# PiHAT.net
KiCad netlist of a schematic drawn in EAGLE
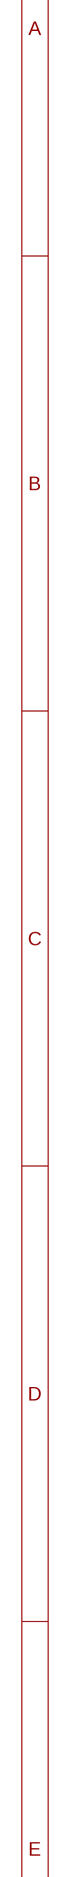
[diagram p0: schematic, sheet 1, part 1 of 2]
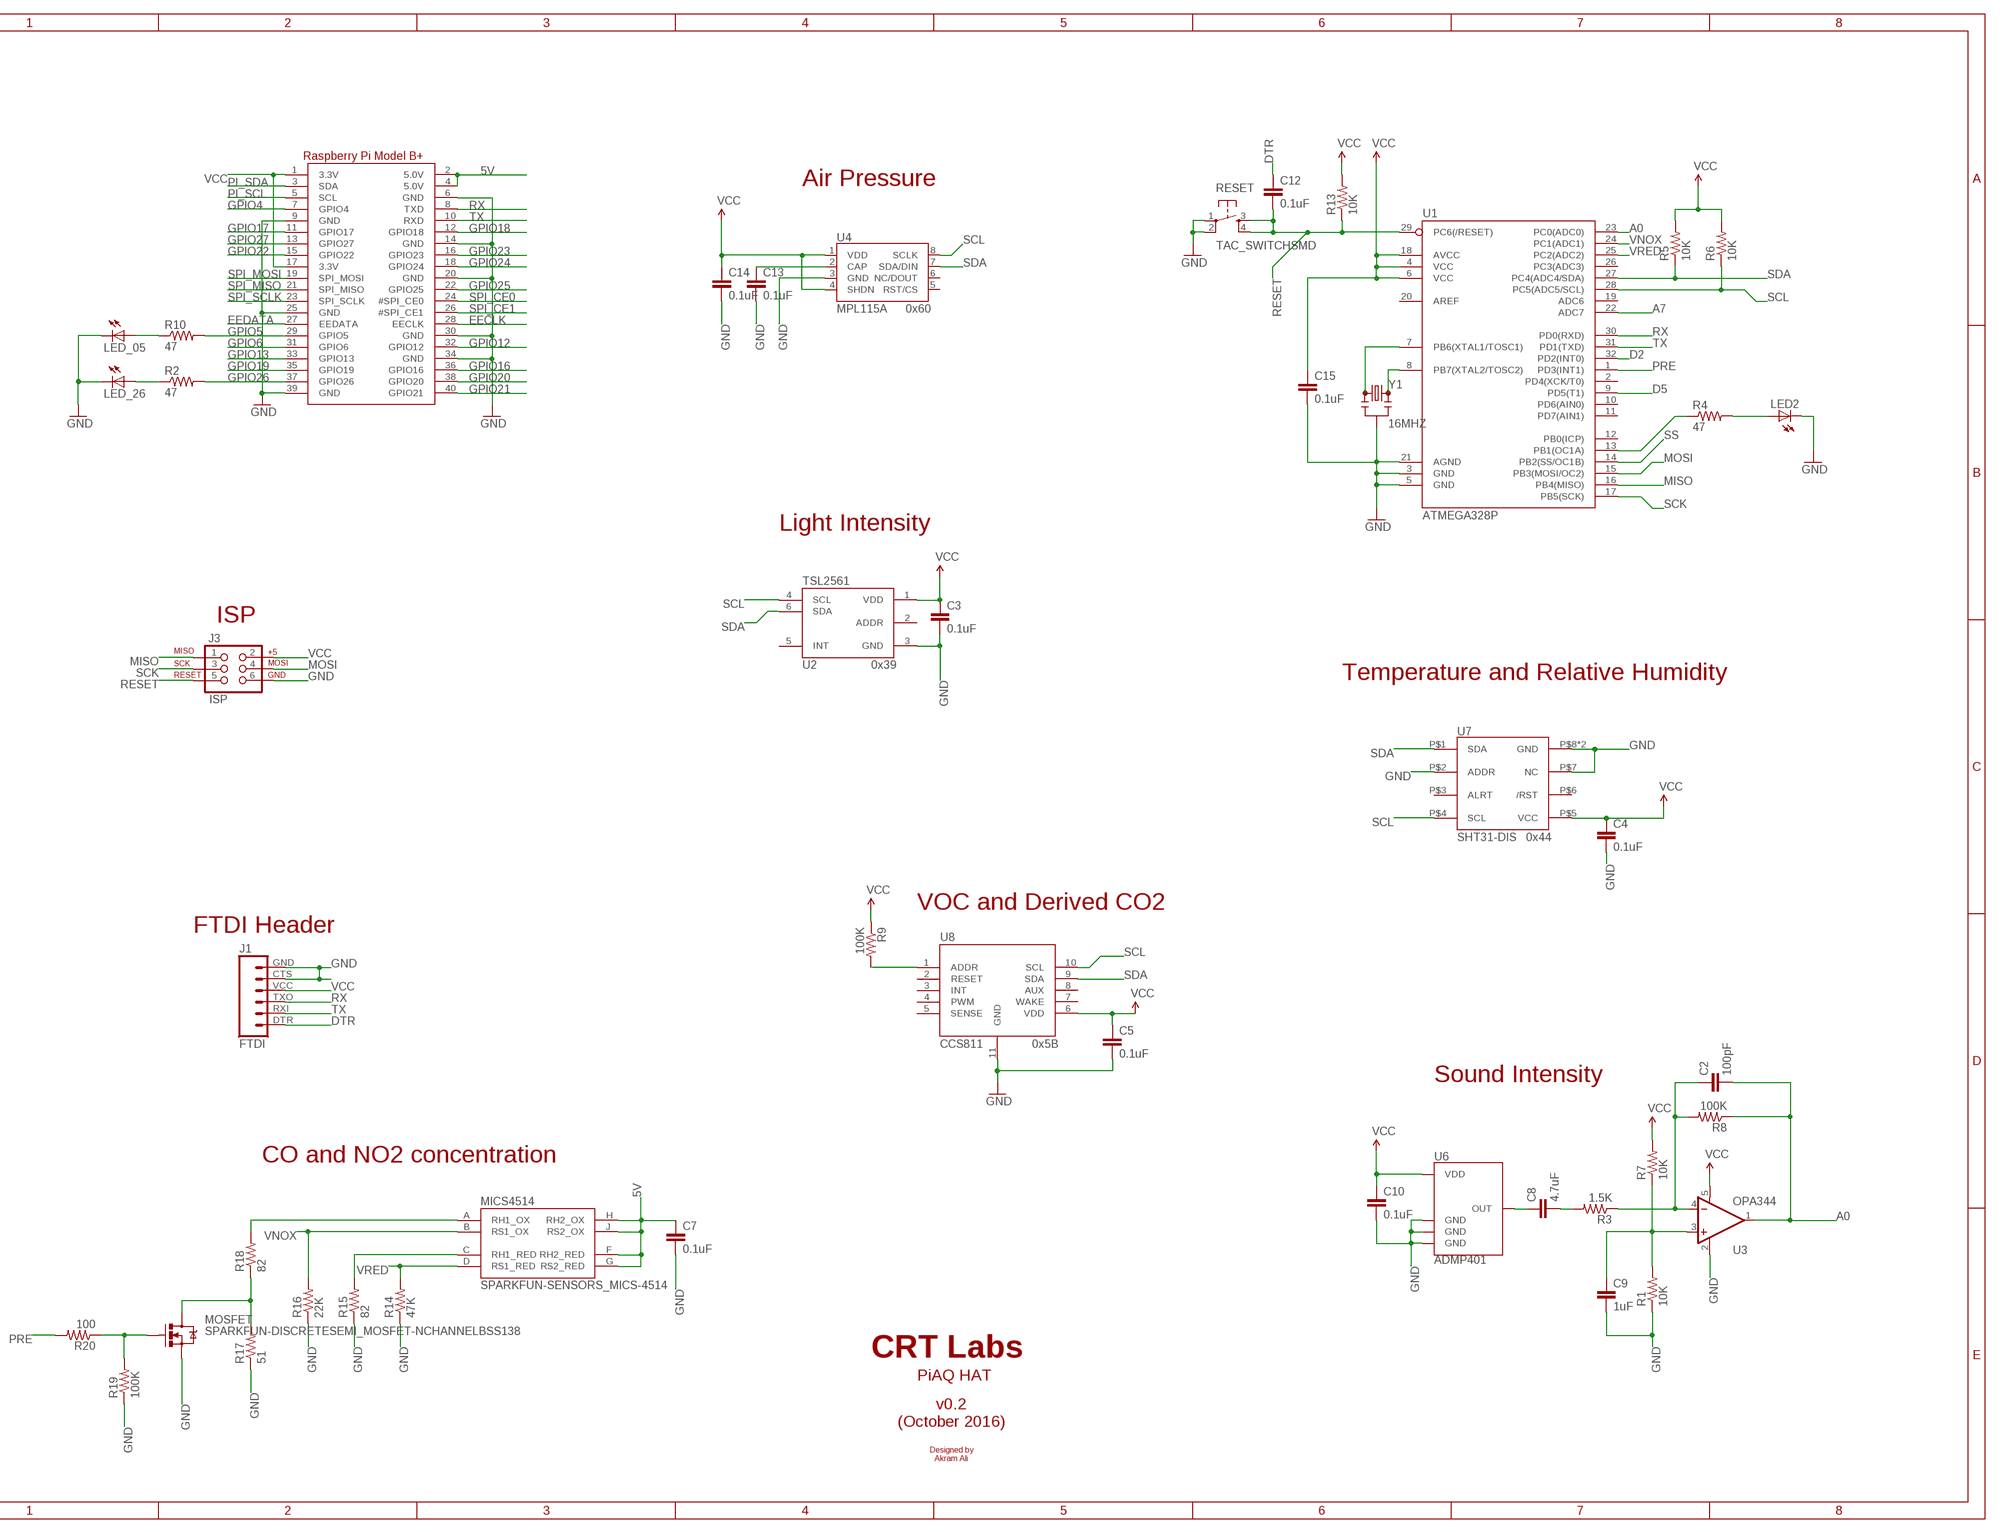
[diagram p1: schematic, sheet 1, part 2 of 2]

(export (version "E")
  (design (tool "Eeschema 10.0.6"))
  (components
    (comp (ref "C2")
      (value "100pF")
      (footprint "eagle-import:0805")
      (fields (field (name "MPN") "CC0805JRNPO9BN101"))
      (libsource (lib "eagle-import") (part "CAP0805"))
    )
    (comp (ref "C3")
      (value "0.1uF")
      (footprint "eagle-import:0805")
      (fields (field (name "MPN") "CC0603KRX7R7BB104"))
      (libsource (lib "eagle-import") (part "SparkFun-Passives_CAP0805"))
    )
    (comp (ref "C4")
      (value "0.1uF")
      (footprint "eagle-import:0805")
      (fields (field (name "MPN") "CC0603KRX7R7BB104"))
      (libsource (lib "eagle-import") (part "SparkFun-Passives_CAP0805"))
    )
    (comp (ref "C5")
      (value "0.1uF")
      (footprint "eagle-import:0805")
      (fields (field (name "MPN") "CC0603KRX7R7BB104"))
      (libsource (lib "eagle-import") (part "SparkFun-Passives_CAP0805"))
    )
    (comp (ref "C7")
      (value "0.1uF")
      (footprint "eagle-import:0805")
      (fields (field (name "MPN") "CC0603KRX7R7BB104"))
      (libsource (lib "eagle-import") (part "SparkFun-Passives_CAP0805"))
    )
    (comp (ref "C8")
      (value "4.7uF")
      (footprint "eagle-import:0805")
      (fields (field (name "MPN") "CC0805KKX5R8BB475"))
      (libsource (lib "eagle-import") (part "CAP0805"))
    )
    (comp (ref "C9")
      (value "1uF")
      (footprint "eagle-import:0805")
      (fields (field (name "MPN") "CC0805KKX7R7BB105"))
      (libsource (lib "eagle-import") (part "CAP0805"))
    )
    (comp (ref "C10")
      (value "0.1uF")
      (footprint "eagle-import:0805")
      (fields (field (name "MPN") "CC0603KRX7R7BB104"))
      (libsource (lib "eagle-import") (part "CAP0805"))
    )
    (comp (ref "C12")
      (value "0.1uF")
      (footprint "eagle-import:0805")
      (fields (field (name "MPN") "CC0603KRX7R7BB104"))
      (libsource (lib "eagle-import") (part "SparkFun-Passives_CAP0805"))
    )
    (comp (ref "C13")
      (value "0.1uF")
      (footprint "eagle-import:0805")
      (fields (field (name "MPN") "CC0603KRX7R7BB104"))
      (libsource (lib "eagle-import") (part "SparkFun-Passives_CAP0805"))
    )
    (comp (ref "C14")
      (value "0.1uF")
      (footprint "eagle-import:0805")
      (fields (field (name "MPN") "CC0603KRX7R7BB104"))
      (libsource (lib "eagle-import") (part "SparkFun-Passives_CAP0805"))
    )
    (comp (ref "C15")
      (value "0.1uF")
      (footprint "eagle-import:0805")
      (fields (field (name "MPN") "CC0603KRX7R7BB104"))
      (libsource (lib "eagle-import") (part "SparkFun-Passives_CAP0805"))
    )
    (comp (ref "J1")
      (value "FTDI")
      (footprint "eagle-import:FTDI_BASIC")
      (fields (field (name "MPN") "FT231XS-R"))
      (libsource (lib "eagle-import") (part "FTDI_BASICPTH"))
    )
    (comp (ref "J3")
      (value "ISP")
      (footprint "eagle-import:2X3")
      (libsource (lib "eagle-import") (part "AVR_SPI_PRG_6PTH"))
    )
    (comp (ref "LED2")
      (value "LEDCHIPLED_0805")
      (footprint "eagle-import:CHIPLED_0805")
      (fields (field (name "MPN") "LY L29K-H1K2-26-Z"))
      (libsource (lib "eagle-import") (part "LEDCHIPLED_0805"))
    )
    (comp (ref "LED_05")
      (value "LEDCHIPLED_0805")
      (footprint "eagle-import:CHIPLED_0805")
      (fields (field (name "MPN") "LY L29K-H1K2-26-Z"))
      (libsource (lib "eagle-import") (part "LEDCHIPLED_0805"))
    )
    (comp (ref "LED_26")
      (value "LEDCHIPLED_0805")
      (footprint "eagle-import:CHIPLED_0805")
      (fields (field (name "MPN") "LY L29K-H1K2-26-Z"))
      (libsource (lib "eagle-import") (part "LEDCHIPLED_0805"))
    )
    (comp (ref "MICS4514")
      (value "SPARKFUN-SENSORS_MICS-4514")
      (footprint "eagle-import:SPARKFUN-SENSORS_MICS_10-SMD")
      (fields (field (name "MANF") "SensorTech") (field (name "MPN") "MiCS-4514"))
      (libsource (lib "eagle-import") (part "SPARKFUN-SENSORS_MICS-4514"))
    )
    (comp (ref "MOSFET")
      (value "SPARKFUN-DISCRETESEMI_MOSFET-NCHANNELBSS138")
      (footprint "eagle-import:SPARKFUN-DISCRETESEMI_SOT23-3")
      (fields (field (name "MPN") "BSS138-7-F"))
      (libsource (lib "eagle-import") (part "SPARKFUN-DISCRETESEMI_MOSFET-NCHANNELBSS138"))
    )
    (comp (ref "R1")
      (value "10K")
      (footprint "eagle-import:0805")
      (fields (field (name "MPN") "RC0805JR-0710KL"))
      (libsource (lib "eagle-import") (part "RESISTOR0805-RES"))
    )
    (comp (ref "R2")
      (value "47")
      (footprint "eagle-import:0805")
      (fields (field (name "MPN") "RC0805JR-0747RL"))
      (libsource (lib "eagle-import") (part "SparkFun-Resistors_RESISTOR0805-RES"))
    )
    (comp (ref "R3")
      (value "1.5K")
      (footprint "eagle-import:0805")
      (fields (field (name "MPN") "RT0805BRD071K5L"))
      (libsource (lib "eagle-import") (part "RESISTOR0805-RES"))
    )
    (comp (ref "R4")
      (value "47")
      (footprint "eagle-import:0805")
      (fields (field (name "MPN") "RC0805JR-0747RL"))
      (libsource (lib "eagle-import") (part "SparkFun-Resistors_RESISTOR0805-RES"))
    )
    (comp (ref "R5")
      (value "10K")
      (footprint "eagle-import:0805")
      (fields (field (name "MPN") "RC0805JR-0710KL"))
      (libsource (lib "eagle-import") (part "SparkFun-Resistors_RESISTOR0805-RES"))
    )
    (comp (ref "R6")
      (value "10K")
      (footprint "eagle-import:0805")
      (fields (field (name "MPN") "RC0805JR-0710KL"))
      (libsource (lib "eagle-import") (part "SparkFun-Resistors_RESISTOR0805-RES"))
    )
    (comp (ref "R7")
      (value "10K")
      (footprint "eagle-import:0805")
      (fields (field (name "MPN") "RC0805JR-0710KL"))
      (libsource (lib "eagle-import") (part "RESISTOR0805-RES"))
    )
    (comp (ref "R8")
      (value "100K")
      (footprint "eagle-import:0805")
      (fields (field (name "MPN") "RC0805FR-07100KL"))
      (libsource (lib "eagle-import") (part "RESISTOR0805-RES"))
    )
    (comp (ref "R9")
      (value "100K")
      (footprint "eagle-import:0805")
      (fields (field (name "MPN") "RC0805FR-07100KL"))
      (libsource (lib "eagle-import") (part "RESISTOR0805-RES"))
    )
    (comp (ref "R10")
      (value "47")
      (footprint "eagle-import:0805")
      (fields (field (name "MPN") "RC0805JR-0747RL"))
      (libsource (lib "eagle-import") (part "SparkFun-Resistors_RESISTOR0805-RES"))
    )
    (comp (ref "R13")
      (value "10K")
      (footprint "eagle-import:0805")
      (fields (field (name "MPN") "RC0805JR-0710KL"))
      (libsource (lib "eagle-import") (part "RESISTOR0805-RES"))
    )
    (comp (ref "R14")
      (value "47K")
      (footprint "eagle-import:0805")
      (fields (field (name "MPN") "ESR10EZPJ473"))
      (libsource (lib "eagle-import") (part "RESISTOR0805-RES"))
    )
    (comp (ref "R15")
      (value "82")
      (footprint "eagle-import:0805")
      (fields (field (name "MPN") "CRCW080582R0FKEA"))
      (libsource (lib "eagle-import") (part "RESISTOR0805-RES"))
    )
    (comp (ref "R16")
      (value "22K")
      (footprint "eagle-import:0805")
      (fields (field (name "MPN") "RC0805JR-0722KL"))
      (libsource (lib "eagle-import") (part "RESISTOR0805-RES"))
    )
    (comp (ref "R17")
      (value "51")
      (footprint "eagle-import:0805")
      (fields (field (name "MPN") "ESR10EZPJ510"))
      (libsource (lib "eagle-import") (part "RESISTOR0805-RES"))
    )
    (comp (ref "R18")
      (value "82")
      (footprint "eagle-import:0805")
      (fields (field (name "MPN") "CRCW080582R0FKEA"))
      (libsource (lib "eagle-import") (part "RESISTOR0805-RES"))
    )
    (comp (ref "R19")
      (value "100K")
      (footprint "eagle-import:0805")
      (fields (field (name "MPN") "RC0805FR-07100KL"))
      (libsource (lib "eagle-import") (part "RESISTOR0805-RES"))
    )
    (comp (ref "R20")
      (value "100")
      (footprint "eagle-import:0805")
      (fields (field (name "MPN") "RC0805FR-07100RL"))
      (libsource (lib "eagle-import") (part "RESISTOR0805-RES"))
    )
    (comp (ref "RESET")
      (value "TAC_SWITCHSMD")
      (footprint "eagle-import:TACTILE-SWITCH-SMD")
      (fields (field (name "MPN") "PTS525SM15SMTR2 LFS"))
      (libsource (lib "eagle-import") (part "TAC_SWITCHSMD"))
    )
    (comp (ref "RPI1")
      (value "RASPBERRYPI_BPLUS_HATSLOTS")
      (footprint "eagle-import:PI_HAT_SLOTS")
      (libsource (lib "eagle-import") (part "RASPBERRYPI_BPLUS_HATSLOTS"))
    )
    (comp (ref "U1")
      (value "ATMEGA328P")
      (footprint "eagle-import:TQFP32-08")
      (fields (field (name "MPN") "ATMEGA328PB-AU"))
      (libsource (lib "eagle-import") (part "ATMEGA328P_TQFP"))
    )
    (comp (ref "U2")
      (value "TSL2561")
      (footprint "eagle-import:FN-6")
      (fields (field (name "MANF") "AMS-TAOS-USA-Inc.") (field (name "MPN") "TSL2561FN"))
      (libsource (lib "eagle-import") (part "TSL2561FN"))
    )
    (comp (ref "U3")
      (value "OPA344")
      (footprint "eagle-import:SOT23-5")
      (fields (field (name "MPN") "OPA344NA/3K"))
      (libsource (lib "eagle-import") (part "OPA344"))
    )
    (comp (ref "U4")
      (value "MPL115A")
      (footprint "eagle-import:LGA8")
      (fields (field (name "MPN") "MPL115A2"))
      (libsource (lib "eagle-import") (part "MPL115A"))
    )
    (comp (ref "U6")
      (value "ADMP401")
      (footprint "eagle-import:ADMP401")
      (fields (field (name "MPN") "INMP401ACEZ-R7"))
      (libsource (lib "eagle-import") (part "ADMP401"))
    )
    (comp (ref "U7")
      (value "SHT31-DIS")
      (footprint "eagle-import:SHT3X")
      (fields (field (name "MPN") "SHT31-DIS-B"))
      (libsource (lib "eagle-import") (part "SHT31-DIS"))
    )
    (comp (ref "U8")
      (value "CCS811")
      (footprint "eagle-import:LGA")
      (fields (field (name "MANF") "AMS"))
      (libsource (lib "eagle-import") (part "CCS811-I2C"))
    )
    (comp (ref "Y1")
      (value "16MHZ")
      (footprint "eagle-import:RESONATOR-SMD")
      (fields (field (name "MPN") "CSTCE16M0V53-R0"))
      (libsource (lib "eagle-import") (part "RESONATOR16MHZ"))
    )
  )
  (nets
    (net (code "1") (name "/EECLK") (class "Default")
      (node (ref "RPI1") (pin "28") (pinfunction "EECLK_28") (pintype "power_in"))
    )
    (net (code "2") (name "/EEDATA") (class "Default")
      (node (ref "RPI1") (pin "27") (pinfunction "EEDATA_27") (pintype "bidirectional"))
    )
    (net (code "3") (name "/GPIO4") (class "Default")
      (node (ref "RPI1") (pin "7") (pinfunction "GPIO4_7") (pintype "bidirectional"))
    )
    (net (code "4") (name "/GPIO5") (class "Default")
      (node (ref "R10") (pin "2") (pinfunction "2_2") (pintype "passive"))
      (node (ref "RPI1") (pin "29") (pinfunction "GPIO5_29") (pintype "bidirectional"))
    )
    (net (code "5") (name "/GPIO6") (class "Default")
      (node (ref "RPI1") (pin "31") (pinfunction "GPIO6_31") (pintype "power_in"))
    )
    (net (code "6") (name "/GPIO12") (class "Default")
      (node (ref "RPI1") (pin "32") (pinfunction "GPIO12_32") (pintype "bidirectional"))
    )
    (net (code "7") (name "/GPIO13") (class "Default")
      (node (ref "RPI1") (pin "33") (pinfunction "GPIO13_33") (pintype "bidirectional"))
    )
    (net (code "8") (name "/GPIO16") (class "Default")
      (node (ref "RPI1") (pin "36") (pinfunction "GPIO16_36") (pintype "power_in"))
    )
    (net (code "9") (name "/GPIO17") (class "Default")
      (node (ref "RPI1") (pin "11") (pinfunction "GPIO17_11") (pintype "bidirectional"))
    )
    (net (code "10") (name "/GPIO18") (class "Default")
      (node (ref "RPI1") (pin "12") (pinfunction "GPIO18_12") (pintype "bidirectional"))
    )
    (net (code "11") (name "/GPIO19") (class "Default")
      (node (ref "RPI1") (pin "35") (pinfunction "GPIO19_35") (pintype "bidirectional"))
    )
    (net (code "12") (name "/GPIO20") (class "Default")
      (node (ref "RPI1") (pin "38") (pinfunction "GPIO20_38") (pintype "bidirectional"))
    )
    (net (code "13") (name "/GPIO21") (class "Default")
      (node (ref "RPI1") (pin "40") (pinfunction "GPIO21_40") (pintype "bidirectional"))
    )
    (net (code "14") (name "/GPIO22") (class "Default")
      (node (ref "RPI1") (pin "15") (pinfunction "GPIO22_15") (pintype "bidirectional"))
    )
    (net (code "15") (name "/GPIO23") (class "Default")
      (node (ref "RPI1") (pin "16") (pinfunction "GPIO23_16") (pintype "bidirectional"))
    )
    (net (code "16") (name "/GPIO24") (class "Default")
      (node (ref "RPI1") (pin "18") (pinfunction "GPIO24_18") (pintype "bidirectional"))
    )
    (net (code "17") (name "/GPIO25") (class "Default")
      (node (ref "RPI1") (pin "22") (pinfunction "GPIO25_22") (pintype "bidirectional"))
    )
    (net (code "18") (name "/GPIO26") (class "Default")
      (node (ref "R2") (pin "2") (pinfunction "2_2") (pintype "passive"))
      (node (ref "RPI1") (pin "37") (pinfunction "GPIO26_37") (pintype "bidirectional"))
    )
    (net (code "19") (name "/GPIO27") (class "Default")
      (node (ref "RPI1") (pin "13") (pinfunction "GPIO27_13") (pintype "bidirectional"))
    )
    (net (code "20") (name "/PI_SCL") (class "Default")
      (node (ref "RPI1") (pin "5") (pinfunction "SCL_5") (pintype "bidirectional"))
    )
    (net (code "21") (name "/PI_SDA") (class "Default")
      (node (ref "RPI1") (pin "3") (pinfunction "SDA_3") (pintype "bidirectional"))
    )
    (net (code "22") (name "/SPI_CE0") (class "Default")
      (node (ref "RPI1") (pin "24") (pinfunction "#SPI_CE0_24") (pintype "bidirectional"))
    )
    (net (code "23") (name "/SPI_CE1") (class "Default")
      (node (ref "RPI1") (pin "26") (pinfunction "#SPI_CE1_26") (pintype "bidirectional"))
    )
    (net (code "24") (name "/SPI_MISO") (class "Default")
      (node (ref "RPI1") (pin "21") (pinfunction "SPI_MISO_21") (pintype "bidirectional"))
    )
    (net (code "25") (name "/SPI_MOSI") (class "Default")
      (node (ref "RPI1") (pin "19") (pinfunction "SPI_MOSI_19") (pintype "bidirectional"))
    )
    (net (code "26") (name "/SPI_SCLK") (class "Default")
      (node (ref "RPI1") (pin "23") (pinfunction "SPI_SCLK_23") (pintype "bidirectional"))
    )
    (net (code "27") (name "5V") (class "Default")
      (node (ref "C7") (pin "1") (pinfunction "1_1") (pintype "passive"))
      (node (ref "MICS4514") (pin "F") (pinfunction "RH2_RED_F") (pintype "bidirectional"))
      (node (ref "MICS4514") (pin "G") (pinfunction "RS2_RED_G") (pintype "bidirectional"))
      (node (ref "MICS4514") (pin "H") (pinfunction "RH2_OX_H") (pintype "bidirectional"))
      (node (ref "MICS4514") (pin "J") (pinfunction "RS2_OX_J") (pintype "bidirectional"))
      (node (ref "RPI1") (pin "2") (pinfunction "5.0V_2") (pintype "power_in"))
      (node (ref "RPI1") (pin "4") (pinfunction "5.0V_4") (pintype "power_in"))
    )
    (net (code "28") (name "A0") (class "Default")
      (node (ref "C2") (pin "2") (pinfunction "2_2") (pintype "passive"))
      (node (ref "R8") (pin "1") (pinfunction "1_1") (pintype "passive"))
      (node (ref "U1") (pin "23") (pinfunction "PC0(ADC0)_23") (pintype "bidirectional"))
      (node (ref "U3") (pin "1") (pinfunction "OUT_1") (pintype "output"))
    )
    (net (code "29") (name "A7") (class "Default")
      (node (ref "U1") (pin "22") (pinfunction "ADC7_22") (pintype "bidirectional"))
    )
    (net (code "30") (name "D2") (class "Default")
      (node (ref "U1") (pin "32") (pinfunction "PD2(INT0)_32") (pintype "bidirectional"))
    )
    (net (code "31") (name "D5") (class "Default")
      (node (ref "U1") (pin "9") (pinfunction "PD5(T1)_9") (pintype "bidirectional"))
    )
    (net (code "32") (name "DTR") (class "Default")
      (node (ref "C12") (pin "1") (pinfunction "1_1") (pintype "passive"))
      (node (ref "J1") (pin "DTR") (pinfunction "1_DTR") (pintype "passive"))
    )
    (net (code "33") (name "GND") (class "Default")
      (node (ref "C10") (pin "2") (pinfunction "2_2") (pintype "passive"))
      (node (ref "C13") (pin "2") (pinfunction "2_2") (pintype "passive"))
      (node (ref "C14") (pin "2") (pinfunction "2_2") (pintype "passive"))
      (node (ref "C15") (pin "2") (pinfunction "2_2") (pintype "passive"))
      (node (ref "C3") (pin "2") (pinfunction "2_2") (pintype "passive"))
      (node (ref "C4") (pin "2") (pinfunction "2_2") (pintype "passive"))
      (node (ref "C5") (pin "2") (pinfunction "2_2") (pintype "passive"))
      (node (ref "C7") (pin "2") (pinfunction "2_2") (pintype "passive"))
      (node (ref "C9") (pin "2") (pinfunction "2_2") (pintype "passive"))
      (node (ref "J1") (pin "CTS") (pinfunction "5_CTS") (pintype "passive"))
      (node (ref "J1") (pin "GND") (pinfunction "6_GND") (pintype "passive"))
      (node (ref "J3") (pin "6") (pinfunction "6_6") (pintype "passive"))
      (node (ref "LED2") (pin "C") (pinfunction "C_C") (pintype "passive"))
      (node (ref "LED_05") (pin "C") (pinfunction "C_C") (pintype "passive"))
      (node (ref "LED_26") (pin "C") (pinfunction "C_C") (pintype "passive"))
      (node (ref "MOSFET") (pin "2") (pinfunction "S_2") (pintype "passive"))
      (node (ref "R1") (pin "1") (pinfunction "1_1") (pintype "passive"))
      (node (ref "R14") (pin "1") (pinfunction "1_1") (pintype "passive"))
      (node (ref "R15") (pin "1") (pinfunction "1_1") (pintype "passive"))
      (node (ref "R16") (pin "1") (pinfunction "1_1") (pintype "passive"))
      (node (ref "R17") (pin "1") (pinfunction "1_1") (pintype "passive"))
      (node (ref "R19") (pin "1") (pinfunction "1_1") (pintype "passive"))
      (node (ref "RESET") (pin "1") (pinfunction "1_1") (pintype "passive"))
      (node (ref "RESET") (pin "2") (pinfunction "2_2") (pintype "passive"))
      (node (ref "RPI1") (pin "14") (pinfunction "GND_14") (pintype "power_in"))
      (node (ref "RPI1") (pin "20") (pinfunction "GND_20") (pintype "power_in"))
      (node (ref "RPI1") (pin "25") (pinfunction "GND_25") (pintype "power_in"))
      (node (ref "RPI1") (pin "30") (pinfunction "GND_30") (pintype "bidirectional"))
      (node (ref "RPI1") (pin "34") (pinfunction "GND_34") (pintype "bidirectional"))
      (node (ref "RPI1") (pin "39") (pinfunction "GND_39") (pintype "power_in"))
      (node (ref "RPI1") (pin "6") (pinfunction "GND_6") (pintype "power_in"))
      (node (ref "RPI1") (pin "9") (pinfunction "GND_9") (pintype "power_in"))
      (node (ref "U1") (pin "21") (pinfunction "AGND_21") (pintype "bidirectional"))
      (node (ref "U1") (pin "3") (pinfunction "GND_3") (pintype "bidirectional"))
      (node (ref "U1") (pin "5") (pinfunction "GND_5") (pintype "bidirectional"))
      (node (ref "U2") (pin "3") (pinfunction "GND_3") (pintype "power_in"))
      (node (ref "U3") (pin "2") (pinfunction "V-_2") (pintype "power_in"))
      (node (ref "U4") (pin "3") (pinfunction "GND_3") (pintype "bidirectional"))
      (node (ref "U6") (pin "2") (pinfunction "GND_2") (pintype "bidirectional"))
      (node (ref "U6") (pin "4") (pinfunction "GND_4") (pintype "bidirectional"))
      (node (ref "U6") (pin "6") (pinfunction "GND_6") (pintype "bidirectional"))
      (node (ref "U7") (pin "P$2") (pinfunction "ADDR_P$2") (pintype "bidirectional"))
      (node (ref "U7") (pin "P$7") (pinfunction "NC_P$7") (pintype "bidirectional"))
      (node (ref "U7") (pin "P$8") (pinfunction "GND_P$8") (pintype "bidirectional"))
      (node (ref "U7") (pin "PAD") (pinfunction "GND_PAD") (pintype "bidirectional"))
      (node (ref "U8") (pin "11") (pinfunction "GND_11") (pintype "bidirectional"))
      (node (ref "Y1") (pin "2") (pinfunction "2_2") (pintype "passive"))
    )
    (net (code "34") (name "MISO") (class "Default")
      (node (ref "J3") (pin "1") (pinfunction "1_1") (pintype "passive"))
      (node (ref "U1") (pin "16") (pinfunction "PB4(MISO)_16") (pintype "bidirectional"))
    )
    (net (code "35") (name "MOSI") (class "Default")
      (node (ref "J3") (pin "4") (pinfunction "4_4") (pintype "passive"))
      (node (ref "U1") (pin "15") (pinfunction "PB3(MOSI/OC2)_15") (pintype "bidirectional"))
    )
    (net (code "36") (name "Net-(C8-Pad2)") (class "Default")
      (node (ref "C8") (pin "2") (pinfunction "2_2") (pintype "passive"))
      (node (ref "R3") (pin "2") (pinfunction "2_2") (pintype "passive"))
    )
    (net (code "37") (name "Net-(LED2-PadA)") (class "Default")
      (node (ref "LED2") (pin "A") (pinfunction "A_A") (pintype "passive"))
      (node (ref "R4") (pin "2") (pinfunction "2_2") (pintype "passive"))
    )
    (net (code "38") (name "Net-(LED_05-PadA)") (class "Default")
      (node (ref "LED_05") (pin "A") (pinfunction "A_A") (pintype "passive"))
      (node (ref "R10") (pin "1") (pinfunction "1_1") (pintype "passive"))
    )
    (net (code "39") (name "Net-(LED_26-PadA)") (class "Default")
      (node (ref "LED_26") (pin "A") (pinfunction "A_A") (pintype "passive"))
      (node (ref "R2") (pin "1") (pinfunction "1_1") (pintype "passive"))
    )
    (net (code "40") (name "Net-(MICS4514-RH1_OX)") (class "Default")
      (node (ref "MICS4514") (pin "A") (pinfunction "RH1_OX_A") (pintype "bidirectional"))
      (node (ref "R18") (pin "2") (pinfunction "2_2") (pintype "passive"))
    )
    (net (code "41") (name "Net-(MICS4514-RH1_RED)") (class "Default")
      (node (ref "MICS4514") (pin "C") (pinfunction "RH1_RED_C") (pintype "bidirectional"))
      (node (ref "R15") (pin "2") (pinfunction "2_2") (pintype "passive"))
    )
    (net (code "42") (name "Net-(MOSFET-D)") (class "Default")
      (node (ref "MOSFET") (pin "3") (pinfunction "D_3") (pintype "passive"))
      (node (ref "R17") (pin "2") (pinfunction "2_2") (pintype "passive"))
      (node (ref "R18") (pin "1") (pinfunction "1_1") (pintype "passive"))
    )
    (net (code "43") (name "Net-(MOSFET-G)") (class "Default")
      (node (ref "MOSFET") (pin "1") (pinfunction "G_1") (pintype "passive"))
      (node (ref "R19") (pin "2") (pinfunction "2_2") (pintype "passive"))
      (node (ref "R20") (pin "1") (pinfunction "1_1") (pintype "passive"))
    )
    (net (code "44") (name "Net-(U1-PB1(OC1A))") (class "Default")
      (node (ref "R4") (pin "1") (pinfunction "1_1") (pintype "passive"))
      (node (ref "U1") (pin "13") (pinfunction "PB1(OC1A)_13") (pintype "bidirectional"))
    )
    (net (code "45") (name "Net-(U1-PB6(XTAL1{slash}TOSC1))") (class "Default")
      (node (ref "U1") (pin "7") (pinfunction "PB6(XTAL1/TOSC1)_7") (pintype "bidirectional"))
      (node (ref "Y1") (pin "1") (pinfunction "1_1") (pintype "passive"))
    )
    (net (code "46") (name "Net-(U1-PB7(XTAL2{slash}TOSC2))") (class "Default")
      (node (ref "U1") (pin "8") (pinfunction "PB7(XTAL2/TOSC2)_8") (pintype "bidirectional"))
      (node (ref "Y1") (pin "3") (pinfunction "3_3") (pintype "passive"))
    )
    (net (code "47") (name "Net-(U3-+IN)") (class "Default")
      (node (ref "C9") (pin "1") (pinfunction "1_1") (pintype "passive"))
      (node (ref "R1") (pin "2") (pinfunction "2_2") (pintype "passive"))
      (node (ref "R7") (pin "1") (pinfunction "1_1") (pintype "passive"))
      (node (ref "U3") (pin "3") (pinfunction "+IN_3") (pintype "input"))
    )
    (net (code "48") (name "Net-(U3--IN)") (class "Default")
      (node (ref "C2") (pin "1") (pinfunction "1_1") (pintype "passive"))
      (node (ref "R3") (pin "1") (pinfunction "1_1") (pintype "passive"))
      (node (ref "R8") (pin "2") (pinfunction "2_2") (pintype "passive"))
      (node (ref "U3") (pin "4") (pinfunction "-IN_4") (pintype "input"))
    )
    (net (code "49") (name "Net-(U4-CAP)") (class "Default")
      (node (ref "C13") (pin "1") (pinfunction "1_1") (pintype "passive"))
      (node (ref "U4") (pin "2") (pinfunction "CAP_2") (pintype "bidirectional"))
    )
    (net (code "50") (name "Net-(U6-OUT)") (class "Default")
      (node (ref "C8") (pin "1") (pinfunction "1_1") (pintype "passive"))
      (node (ref "U6") (pin "1") (pinfunction "OUT_1") (pintype "bidirectional"))
    )
    (net (code "51") (name "Net-(U8-ADDR)") (class "Default")
      (node (ref "R9") (pin "2") (pinfunction "2_2") (pintype "passive"))
      (node (ref "U8") (pin "1") (pinfunction "ADDR_1") (pintype "bidirectional"))
    )
    (net (code "52") (name "PRE") (class "Default")
      (node (ref "R20") (pin "2") (pinfunction "2_2") (pintype "passive"))
      (node (ref "U1") (pin "1") (pinfunction "PD3(INT1)_1") (pintype "bidirectional"))
    )
    (net (code "53") (name "RESET") (class "Default")
      (node (ref "C12") (pin "2") (pinfunction "2_2") (pintype "passive"))
      (node (ref "J3") (pin "5") (pinfunction "5_5") (pintype "passive"))
      (node (ref "R13") (pin "1") (pinfunction "1_1") (pintype "passive"))
      (node (ref "RESET") (pin "3") (pinfunction "3_3") (pintype "passive"))
      (node (ref "RESET") (pin "4") (pinfunction "4_4") (pintype "passive"))
      (node (ref "U1") (pin "29") (pinfunction "PC6(/RESET)_29") (pintype "bidirectional"))
    )
    (net (code "54") (name "RX") (class "Default")
      (node (ref "J1") (pin "TXO") (pinfunction "3_TXO") (pintype "passive"))
      (node (ref "RPI1") (pin "8") (pinfunction "TXD_8") (pintype "output"))
      (node (ref "U1") (pin "30") (pinfunction "PD0(RXD)_30") (pintype "bidirectional"))
    )
    (net (code "55") (name "SCK") (class "Default")
      (node (ref "J3") (pin "3") (pinfunction "3_3") (pintype "passive"))
      (node (ref "U1") (pin "17") (pinfunction "PB5(SCK)_17") (pintype "bidirectional"))
    )
    (net (code "56") (name "SCL") (class "Default")
      (node (ref "R6") (pin "1") (pinfunction "1_1") (pintype "passive"))
      (node (ref "U1") (pin "28") (pinfunction "PC5(ADC5/SCL)_28") (pintype "bidirectional"))
      (node (ref "U2") (pin "4") (pinfunction "SCL_4") (pintype "input"))
      (node (ref "U4") (pin "8") (pinfunction "SCLK_8") (pintype "bidirectional"))
      (node (ref "U7") (pin "P$4") (pinfunction "SCL_P$4") (pintype "bidirectional"))
      (node (ref "U8") (pin "10") (pinfunction "SCL_10") (pintype "bidirectional"))
    )
    (net (code "57") (name "SDA") (class "Default")
      (node (ref "R5") (pin "1") (pinfunction "1_1") (pintype "passive"))
      (node (ref "U1") (pin "27") (pinfunction "PC4(ADC4/SDA)_27") (pintype "bidirectional"))
      (node (ref "U2") (pin "6") (pinfunction "SDA_6") (pintype "bidirectional"))
      (node (ref "U4") (pin "7") (pinfunction "SDA/DIN_7") (pintype "bidirectional"))
      (node (ref "U7") (pin "P$1") (pinfunction "SDA_P$1") (pintype "bidirectional"))
      (node (ref "U8") (pin "9") (pinfunction "SDA_9") (pintype "bidirectional"))
    )
    (net (code "58") (name "SS") (class "Default")
      (node (ref "U1") (pin "14") (pinfunction "PB2(SS/OC1B)_14") (pintype "bidirectional"))
    )
    (net (code "59") (name "TX") (class "Default")
      (node (ref "J1") (pin "RXI") (pinfunction "2_RXI") (pintype "passive"))
      (node (ref "RPI1") (pin "10") (pinfunction "RXD_10") (pintype "bidirectional"))
      (node (ref "U1") (pin "31") (pinfunction "PD1(TXD)_31") (pintype "bidirectional"))
    )
    (net (code "60") (name "VCC") (class "Default")
      (node (ref "C10") (pin "1") (pinfunction "1_1") (pintype "passive"))
      (node (ref "C14") (pin "1") (pinfunction "1_1") (pintype "passive"))
      (node (ref "C15") (pin "1") (pinfunction "1_1") (pintype "passive"))
      (node (ref "C3") (pin "1") (pinfunction "1_1") (pintype "passive"))
      (node (ref "C4") (pin "1") (pinfunction "1_1") (pintype "passive"))
      (node (ref "C5") (pin "1") (pinfunction "1_1") (pintype "passive"))
      (node (ref "J1") (pin "VCC") (pinfunction "4_VCC") (pintype "passive"))
      (node (ref "J3") (pin "2") (pinfunction "2_2") (pintype "passive"))
      (node (ref "R13") (pin "2") (pinfunction "2_2") (pintype "passive"))
      (node (ref "R5") (pin "2") (pinfunction "2_2") (pintype "passive"))
      (node (ref "R6") (pin "2") (pinfunction "2_2") (pintype "passive"))
      (node (ref "R7") (pin "2") (pinfunction "2_2") (pintype "passive"))
      (node (ref "R9") (pin "1") (pinfunction "1_1") (pintype "passive"))
      (node (ref "RPI1") (pin "1") (pinfunction "3.3V_1") (pintype "power_in"))
      (node (ref "RPI1") (pin "17") (pinfunction "3.3V_17") (pintype "power_in"))
      (node (ref "U1") (pin "18") (pinfunction "AVCC_18") (pintype "bidirectional"))
      (node (ref "U1") (pin "4") (pinfunction "VCC_4") (pintype "bidirectional"))
      (node (ref "U1") (pin "6") (pinfunction "VCC_6") (pintype "bidirectional"))
      (node (ref "U2") (pin "1") (pinfunction "VDD_1") (pintype "power_in"))
      (node (ref "U3") (pin "5") (pinfunction "V+_5") (pintype "power_in"))
      (node (ref "U4") (pin "1") (pinfunction "VDD_1") (pintype "bidirectional"))
      (node (ref "U4") (pin "4") (pinfunction "SHDN_4") (pintype "bidirectional"))
      (node (ref "U6") (pin "5") (pinfunction "VDD_5") (pintype "bidirectional"))
      (node (ref "U7") (pin "P$5") (pinfunction "VCC_P$5") (pintype "bidirectional"))
      (node (ref "U8") (pin "6") (pinfunction "VDD_6") (pintype "bidirectional"))
    )
    (net (code "61") (name "VNOX") (class "Default")
      (node (ref "MICS4514") (pin "B") (pinfunction "RS1_OX_B") (pintype "bidirectional"))
      (node (ref "R16") (pin "2") (pinfunction "2_2") (pintype "passive"))
      (node (ref "U1") (pin "24") (pinfunction "PC1(ADC1)_24") (pintype "bidirectional"))
    )
    (net (code "62") (name "VRED") (class "Default")
      (node (ref "MICS4514") (pin "D") (pinfunction "RS1_RED_D") (pintype "bidirectional"))
      (node (ref "R14") (pin "2") (pinfunction "2_2") (pintype "passive"))
      (node (ref "U1") (pin "25") (pinfunction "PC2(ADC2)_25") (pintype "bidirectional"))
    )
    (net (code "63") (name "unconnected-(U1-ADC6-Pad19)") (class "Default")
      (node (ref "U1") (pin "19") (pinfunction "ADC6_19") (pintype "bidirectional"))
    )
    (net (code "64") (name "unconnected-(U1-AREF-Pad20)") (class "Default")
      (node (ref "U1") (pin "20") (pinfunction "AREF_20") (pintype "bidirectional"))
    )
    (net (code "65") (name "unconnected-(U1-PB0(ICP)-Pad12)") (class "Default")
      (node (ref "U1") (pin "12") (pinfunction "PB0(ICP)_12") (pintype "bidirectional"))
    )
    (net (code "66") (name "unconnected-(U1-PC3(ADC3)-Pad26)") (class "Default")
      (node (ref "U1") (pin "26") (pinfunction "PC3(ADC3)_26") (pintype "bidirectional"))
    )
    (net (code "67") (name "unconnected-(U1-PD4(XCK{slash}T0)-Pad2)") (class "Default")
      (node (ref "U1") (pin "2") (pinfunction "PD4(XCK/T0)_2") (pintype "bidirectional"))
    )
    (net (code "68") (name "unconnected-(U1-PD6(AIN0)-Pad10)") (class "Default")
      (node (ref "U1") (pin "10") (pinfunction "PD6(AIN0)_10") (pintype "bidirectional"))
    )
    (net (code "69") (name "unconnected-(U1-PD7(AIN1)-Pad11)") (class "Default")
      (node (ref "U1") (pin "11") (pinfunction "PD7(AIN1)_11") (pintype "bidirectional"))
    )
    (net (code "70") (name "unconnected-(U2-ADDR-Pad2)") (class "Default")
      (node (ref "U2") (pin "2") (pinfunction "ADDR_2") (pintype "input"))
    )
    (net (code "71") (name "unconnected-(U2-INT-Pad5)") (class "Default")
      (node (ref "U2") (pin "5") (pinfunction "INT_5") (pintype "output"))
    )
    (net (code "72") (name "unconnected-(U4-NC{slash}DOUT-Pad6)") (class "Default")
      (node (ref "U4") (pin "6") (pinfunction "NC/DOUT_6") (pintype "bidirectional"))
    )
    (net (code "73") (name "unconnected-(U4-RST{slash}CS-Pad5)") (class "Default")
      (node (ref "U4") (pin "5") (pinfunction "RST/CS_5") (pintype "bidirectional"))
    )
    (net (code "74") (name "unconnected-(U7-ALRT-PadP$3)") (class "Default")
      (node (ref "U7") (pin "P$3") (pinfunction "ALRT_P$3") (pintype "bidirectional"))
    )
    (net (code "75") (name "unconnected-(U7-{slash}RST-PadP$6)") (class "Default")
      (node (ref "U7") (pin "P$6") (pinfunction "/RST_P$6") (pintype "bidirectional"))
    )
    (net (code "76") (name "unconnected-(U8-AUX-Pad8)") (class "Default")
      (node (ref "U8") (pin "8") (pinfunction "AUX_8") (pintype "bidirectional"))
    )
    (net (code "77") (name "unconnected-(U8-INT-Pad3)") (class "Default")
      (node (ref "U8") (pin "3") (pinfunction "INT_3") (pintype "bidirectional"))
    )
    (net (code "78") (name "unconnected-(U8-PWM-Pad4)") (class "Default")
      (node (ref "U8") (pin "4") (pinfunction "PWM_4") (pintype "bidirectional"))
    )
    (net (code "79") (name "unconnected-(U8-RESET-Pad2)") (class "Default")
      (node (ref "U8") (pin "2") (pinfunction "RESET_2") (pintype "bidirectional"))
    )
    (net (code "80") (name "unconnected-(U8-SENSE-Pad5)") (class "Default")
      (node (ref "U8") (pin "5") (pinfunction "SENSE_5") (pintype "bidirectional"))
    )
    (net (code "81") (name "unconnected-(U8-WAKE-Pad7)") (class "Default")
      (node (ref "U8") (pin "7") (pinfunction "WAKE_7") (pintype "bidirectional"))
    )
  )
)
